# BOOST.net
KiCad netlist of a schematic drawn in Altium Designer
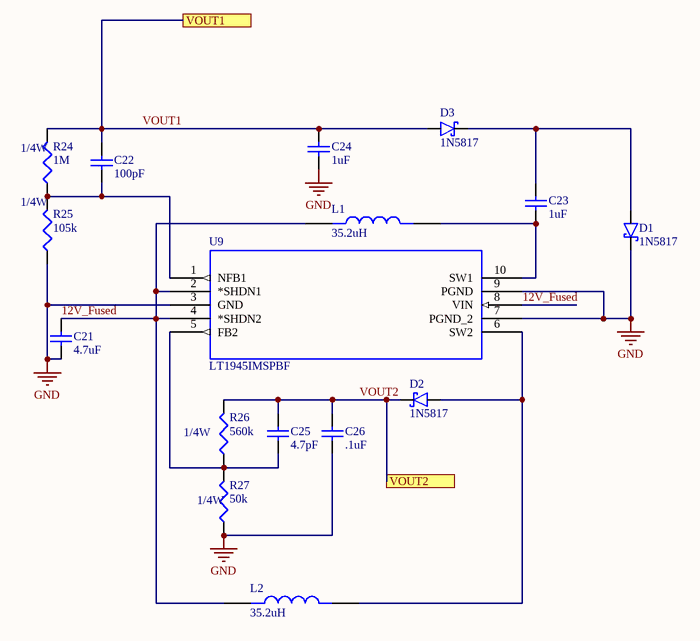
[diagram p0: BOOST.SchDoc]

(export (version "E")
  (design (tool "Eeschema 10.0.6"))
  (components
    (comp (ref "C21")
      (value "4.7uF")
      (footprint "Cap, 5mm TH, Ceramic")
      (description "Generic Cap, 5MM TH, Ceramic")
      (fields (field (name "PUBLISHER") "T.Tallo"))
      (libsource (lib "Passives") (part "Cap, 5MM TH, Ceramic"))
    )
    (comp (ref "C22")
      (value "100pF")
      (footprint "Cap, 5mm TH, Ceramic")
      (description "Generic Cap, 5MM TH, Ceramic")
      (fields (field (name "PUBLISHER") "T.Tallo"))
      (libsource (lib "Passives") (part "Cap, 5MM TH, Ceramic"))
    )
    (comp (ref "C23")
      (value "1uF")
      (footprint "Cap, 5mm TH, Ceramic")
      (description "Generic Cap, 5MM TH, Ceramic")
      (fields (field (name "PUBLISHER") "T.Tallo"))
      (libsource (lib "Passives") (part "Cap, 5MM TH, Ceramic"))
    )
    (comp (ref "C24")
      (value "1uF")
      (footprint "Cap, 5mm TH, Ceramic")
      (description "Generic Cap, 5MM TH, Ceramic")
      (fields (field (name "PUBLISHER") "T.Tallo"))
      (libsource (lib "Passives") (part "Cap, 5MM TH, Ceramic"))
    )
    (comp (ref "C25")
      (value "4.7pF")
      (footprint "Cap, 5mm TH, Ceramic")
      (description "Generic Cap, 5MM TH, Ceramic")
      (fields (field (name "PUBLISHER") "T.Tallo"))
      (libsource (lib "Passives") (part "Cap, 5MM TH, Ceramic"))
    )
    (comp (ref "C26")
      (value ".1uF")
      (footprint "Cap, 5mm TH, Ceramic")
      (description "Generic Cap, 5MM TH, Ceramic")
      (fields (field (name "PUBLISHER") "T.Tallo"))
      (libsource (lib "Passives") (part "Cap, 5MM TH, Ceramic"))
    )
    (comp (ref "D1")
      (value "1N5817")
      (footprint "Diode, TH")
      (description "5A SCHOTTKY RECTIFIER")
      (fields (field (name "MF") "STMicroelectronics"))
      (libsource (lib "") (part "1N5817_1"))
    )
    (comp (ref "D2")
      (value "1N5817")
      (footprint "Diode, TH")
      (description "5A SCHOTTKY RECTIFIER")
      (fields (field (name "MF") "STMicroelectronics"))
      (libsource (lib "") (part "1N5817_1"))
    )
    (comp (ref "D3")
      (value "1N5817")
      (footprint "Diode, TH")
      (description "5A SCHOTTKY RECTIFIER")
      (fields (field (name "MF") "STMicroelectronics"))
      (libsource (lib "BMS_MasterboardUpdated") (part "1N5817"))
    )
    (comp (ref "L1")
      (value "35.2uH")
      (footprint "IND_LQH5BPB220MT0L")
      (description "22ÂµH Shielded Wirewound Inductor 1.05A 310.8mOhm Max Nonstandard")
      (fields (field (name "MP") "LQH5BPB220MT0L") (field (name "MF") "Murata"))
      (libsource (lib "BMS_MasterboardUpdated") (part "LQH5BPB220MT0L"))
    )
    (comp (ref "L2")
      (value "35.2uH")
      (footprint "IND_LQH5BPB220MT0L")
      (description "22ÂµH Shielded Wirewound Inductor 1.05A 310.8mOhm Max Nonstandard")
      (fields (field (name "MP") "LQH5BPB220MT0L") (field (name "MF") "Murata"))
      (libsource (lib "BMS_MasterboardUpdated") (part "LQH5BPB220MT0L"))
    )
    (comp (ref "R24")
      (value "1M")
      (footprint "RESAD640W45L370D200 - duplicate")
      (description "Generic TH Resistor")
      (fields (field (name "PUBLISHER") "T.Tallo"))
      (libsource (lib "Passives") (part "Resistor, TH"))
    )
    (comp (ref "R25")
      (value "105k")
      (footprint "RESAD640W45L370D200 - duplicate")
      (description "Generic TH Resistor")
      (fields (field (name "PUBLISHER") "T.Tallo"))
      (libsource (lib "Passives") (part "Resistor, TH"))
    )
    (comp (ref "R26")
      (value "560k")
      (footprint "RESAD640W45L370D200 - duplicate")
      (description "Generic TH Resistor")
      (fields (field (name "PUBLISHER") "T.Tallo"))
      (libsource (lib "Passives") (part "Resistor, TH"))
    )
    (comp (ref "R27")
      (value "50k")
      (footprint "RESAD640W45L370D200 - duplicate")
      (description "Generic TH Resistor")
      (fields (field (name "PUBLISHER") "T.Tallo"))
      (libsource (lib "Passives") (part "Resistor, TH"))
    )
    (comp (ref "U9")
      (value "LT1945IMSPBF")
      (footprint "MSOP-10_MS")
      (fields (field (name "MF") "Linear Technology/Analog Devices") (field (name "MP") "LT1945IMS#PBF"))
      (libsource (lib "BMS_MasterboardUpdated") (part "LT1945IMSPBF"))
    )
  )
  (nets
    (net (code "1") (name "/12V_Fused") (class "Default")
      (node (ref "C21") (pin "2") (pinfunction "Neg_2") (pintype "passive"))
      (node (ref "L1") (pin "1") (pinfunction "1_1") (pintype "passive"))
      (node (ref "L2") (pin "1") (pinfunction "1_1") (pintype "passive"))
      (node (ref "U9") (pin "2") (pinfunction "*SHDN1_2") (pintype "passive"))
      (node (ref "U9") (pin "4") (pinfunction "*SHDN2_4") (pintype "passive"))
      (node (ref "U9") (pin "8") (pinfunction "VIN_8") (pintype "input"))
    )
    (net (code "2") (name "/VOUT1") (class "Default")
      (node (ref "C22") (pin "2") (pinfunction "Neg_2") (pintype "passive"))
      (node (ref "C24") (pin "2") (pinfunction "Neg_2") (pintype "passive"))
      (node (ref "D3") (pin "1") (pintype "passive"))
      (node (ref "R24") (pin "2") (pinfunction "2_2") (pintype "passive"))
    )
    (net (code "3") (name "/VOUT2") (class "Default")
      (node (ref "C25") (pin "2") (pinfunction "Neg_2") (pintype "passive"))
      (node (ref "C26") (pin "2") (pinfunction "Neg_2") (pintype "passive"))
      (node (ref "D2") (pin "2") (pintype "passive"))
      (node (ref "R26") (pin "2") (pinfunction "2_2") (pintype "passive"))
    )
    (net (code "4") (name "GND") (class "Default")
      (node (ref "C21") (pin "1") (pinfunction "Pos_1") (pintype "passive"))
      (node (ref "C24") (pin "1") (pinfunction "Pos_1") (pintype "passive"))
      (node (ref "C26") (pin "1") (pinfunction "Pos_1") (pintype "passive"))
      (node (ref "D1") (pin "2") (pintype "passive"))
      (node (ref "R25") (pin "1") (pinfunction "1_1") (pintype "passive"))
      (node (ref "R27") (pin "1") (pinfunction "1_1") (pintype "passive"))
      (node (ref "U9") (pin "3") (pinfunction "GND_3") (pintype "power_in"))
      (node (ref "U9") (pin "7") (pinfunction "PGND_2_7") (pintype "power_in"))
      (node (ref "U9") (pin "9") (pinfunction "PGND_9") (pintype "power_in"))
    )
    (net (code "5") (name "Net-(C22-Pos)") (class "Default")
      (node (ref "C22") (pin "1") (pinfunction "Pos_1") (pintype "passive"))
      (node (ref "R24") (pin "1") (pinfunction "1_1") (pintype "passive"))
      (node (ref "R25") (pin "2") (pinfunction "2_2") (pintype "passive"))
      (node (ref "U9") (pin "1") (pinfunction "NFB1_1") (pintype "output"))
    )
    (net (code "6") (name "Net-(C23-Neg)") (class "Default")
      (node (ref "C23") (pin "2") (pinfunction "Neg_2") (pintype "passive"))
      (node (ref "D1") (pin "1") (pintype "passive"))
      (node (ref "D3") (pin "2") (pintype "passive"))
    )
    (net (code "7") (name "Net-(C23-Pos)") (class "Default")
      (node (ref "C23") (pin "1") (pinfunction "Pos_1") (pintype "passive"))
      (node (ref "L1") (pin "2") (pinfunction "2_2") (pintype "passive"))
      (node (ref "U9") (pin "10") (pinfunction "SW1_10") (pintype "passive"))
    )
    (net (code "8") (name "Net-(C25-Pos)") (class "Default")
      (node (ref "C25") (pin "1") (pinfunction "Pos_1") (pintype "passive"))
      (node (ref "R26") (pin "1") (pinfunction "1_1") (pintype "passive"))
      (node (ref "R27") (pin "2") (pinfunction "2_2") (pintype "passive"))
      (node (ref "U9") (pin "5") (pinfunction "FB2_5") (pintype "output"))
    )
    (net (code "9") (name "Net-(U9-SW2)") (class "Default")
      (node (ref "D2") (pin "1") (pintype "passive"))
      (node (ref "L2") (pin "2") (pinfunction "2_2") (pintype "passive"))
      (node (ref "U9") (pin "6") (pinfunction "SW2_6") (pintype "passive"))
    )
  )
)
